# 0_TOP.net
KiCad netlist of a schematic drawn in Altium Designer
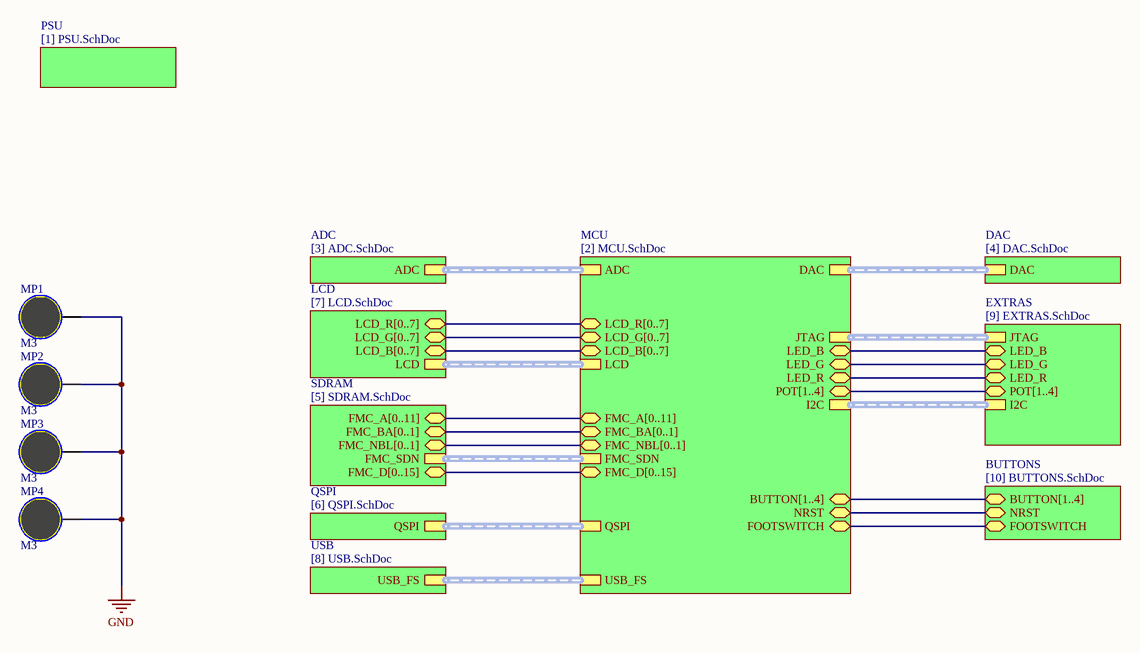
[diagram p0: [0] TOP.SchDoc]

(export (version "E")
  (design (tool "Eeschema 10.0.6"))
  (components
    (comp (ref "MP1")
      (value "M3")
      (footprint "STguitar:Mechanical screw M3")
      (libsource (lib "STguitar") (part "Mechanical screw M3"))
    )
    (comp (ref "MP2")
      (value "M3")
      (footprint "STguitar:Mechanical screw M3")
      (libsource (lib "STguitar") (part "Mechanical screw M3"))
    )
    (comp (ref "MP3")
      (value "M3")
      (footprint "STguitar:Mechanical screw M3")
      (libsource (lib "STguitar") (part "Mechanical screw M3"))
    )
    (comp (ref "MP4")
      (value "M3")
      (footprint "STguitar:Mechanical screw M3")
      (libsource (lib "STguitar") (part "Mechanical screw M3"))
    )
  )
  (nets
    (net (code "23") (name "GND") (class "Default")
      (node (ref "MP1") (pin "0") (pinfunction "0_0") (pintype "passive"))
      (node (ref "MP2") (pin "0") (pinfunction "0_0") (pintype "passive"))
      (node (ref "MP3") (pin "0") (pinfunction "0_0") (pintype "passive"))
      (node (ref "MP4") (pin "0") (pinfunction "0_0") (pintype "passive"))
    )
  )
)
